# temperature.net
KiCad netlist of a schematic drawn in EAGLE
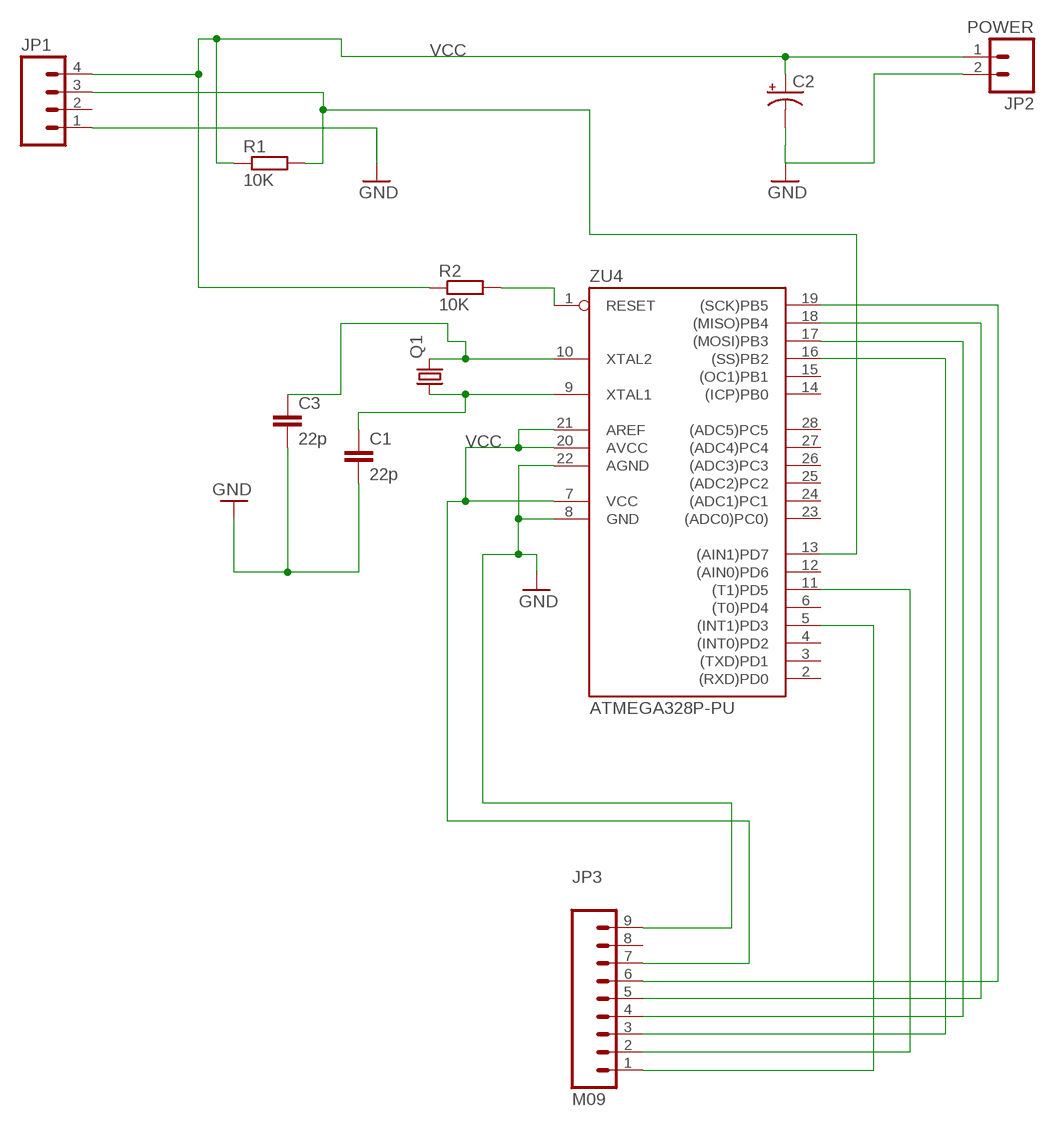
[diagram p0: schematic, sheet 1]

(export (version "E")
  (design (tool "Eeschema 10.0.6"))
  (components
    (comp (ref "C1")
      (value "22p")
      (footprint "eagle-import:C050-025X075")
      (libsource (lib "eagle-import") (part "C-EU050-025X075"))
    )
    (comp (ref "C2")
      (value "CAP_POLPTH1")
      (footprint "eagle-import:CPOL-RADIAL-100UF-25V")
      (libsource (lib "eagle-import") (part "CAP_POLPTH1"))
    )
    (comp (ref "C3")
      (value "22p")
      (footprint "eagle-import:C050-025X075")
      (libsource (lib "eagle-import") (part "C-EU050-025X075"))
    )
    (comp (ref "JP1")
      (value "M04PTH")
      (footprint "eagle-import:1X04")
      (libsource (lib "eagle-import") (part "M04PTH"))
    )
    (comp (ref "JP2")
      (value "POWER")
      (footprint "eagle-import:1X02")
      (libsource (lib "eagle-import") (part "M02PTH"))
    )
    (comp (ref "JP3")
      (value "M09")
      (footprint "eagle-import:1X09")
      (libsource (lib "eagle-import") (part "M09"))
    )
    (comp (ref "Q1")
      (value "CRYSTALHC49S")
      (footprint "eagle-import:HC49_S")
      (libsource (lib "eagle-import") (part "CRYSTALHC49S"))
    )
    (comp (ref "R1")
      (value "10K")
      (footprint "eagle-import:0207_7")
      (libsource (lib "eagle-import") (part "R-EU_0207/7"))
    )
    (comp (ref "R2")
      (value "10K")
      (footprint "eagle-import:0207_7")
      (libsource (lib "eagle-import") (part "R-EU_0207/7"))
    )
    (comp (ref "ZU4")
      (value "ATMEGA328P-PU")
      (footprint "eagle-import:DIL28-3")
      (libsource (lib "eagle-import") (part "ATMEGA328P-PU"))
    )
  )
  (nets
    (net (code "1") (name "/VCC") (class "Default")
      (node (ref "C2") (pin "1") (pinfunction "+_1") (pintype "passive"))
      (node (ref "JP1") (pin "4") (pinfunction "4_4") (pintype "passive"))
      (node (ref "JP2") (pin "1") (pinfunction "1_1") (pintype "passive"))
      (node (ref "JP3") (pin "7") (pinfunction "7_7") (pintype "passive"))
      (node (ref "R1") (pin "1") (pinfunction "1_1") (pintype "passive"))
      (node (ref "R2") (pin "1") (pinfunction "1_1") (pintype "passive"))
      (node (ref "ZU4") (pin "20") (pinfunction "AVCC_20") (pintype "power_in"))
      (node (ref "ZU4") (pin "21") (pinfunction "AREF_21") (pintype "passive"))
      (node (ref "ZU4") (pin "7") (pinfunction "VCC_7") (pintype "power_in"))
    )
    (net (code "2") (name "GND") (class "Default")
      (node (ref "C1") (pin "2") (pinfunction "2_2") (pintype "passive"))
      (node (ref "C2") (pin "2") (pinfunction "-_2") (pintype "passive"))
      (node (ref "C3") (pin "2") (pinfunction "2_2") (pintype "passive"))
      (node (ref "JP1") (pin "1") (pinfunction "1_1") (pintype "passive"))
      (node (ref "JP2") (pin "2") (pinfunction "2_2") (pintype "passive"))
      (node (ref "JP3") (pin "9") (pinfunction "9_9") (pintype "passive"))
      (node (ref "ZU4") (pin "22") (pinfunction "AGND_22") (pintype "power_in"))
      (node (ref "ZU4") (pin "8") (pinfunction "GND_8") (pintype "power_in"))
    )
    (net (code "3") (name "Net-(ZU4-(AIN1)PD7)") (class "Default")
      (node (ref "JP1") (pin "3") (pinfunction "3_3") (pintype "passive"))
      (node (ref "R1") (pin "2") (pinfunction "2_2") (pintype "passive"))
      (node (ref "ZU4") (pin "13") (pinfunction "(AIN1)PD7_13") (pintype "bidirectional"))
    )
    (net (code "4") (name "Net-(ZU4-(INT1)PD3)") (class "Default")
      (node (ref "JP3") (pin "1") (pinfunction "1_1") (pintype "passive"))
      (node (ref "ZU4") (pin "5") (pinfunction "(INT1)PD3_5") (pintype "bidirectional"))
    )
    (net (code "5") (name "Net-(ZU4-(MISO)PB4)") (class "Default")
      (node (ref "JP3") (pin "5") (pinfunction "5_5") (pintype "passive"))
      (node (ref "ZU4") (pin "18") (pinfunction "(MISO)PB4_18") (pintype "bidirectional"))
    )
    (net (code "6") (name "Net-(ZU4-(MOSI)PB3)") (class "Default")
      (node (ref "JP3") (pin "4") (pinfunction "4_4") (pintype "passive"))
      (node (ref "ZU4") (pin "17") (pinfunction "(MOSI)PB3_17") (pintype "bidirectional"))
    )
    (net (code "7") (name "Net-(ZU4-(SCK)PB5)") (class "Default")
      (node (ref "JP3") (pin "6") (pinfunction "6_6") (pintype "passive"))
      (node (ref "ZU4") (pin "19") (pinfunction "(SCK)PB5_19") (pintype "bidirectional"))
    )
    (net (code "8") (name "Net-(ZU4-(SS)PB2)") (class "Default")
      (node (ref "JP3") (pin "3") (pinfunction "3_3") (pintype "passive"))
      (node (ref "ZU4") (pin "16") (pinfunction "(SS)PB2_16") (pintype "bidirectional"))
    )
    (net (code "9") (name "Net-(ZU4-(T1)PD5)") (class "Default")
      (node (ref "JP3") (pin "2") (pinfunction "2_2") (pintype "passive"))
      (node (ref "ZU4") (pin "11") (pinfunction "(T1)PD5_11") (pintype "bidirectional"))
    )
    (net (code "10") (name "Net-(ZU4-RESET)") (class "Default")
      (node (ref "R2") (pin "2") (pinfunction "2_2") (pintype "passive"))
      (node (ref "ZU4") (pin "1") (pinfunction "RESET_1") (pintype "input"))
    )
    (net (code "11") (name "Net-(ZU4-XTAL1)") (class "Default")
      (node (ref "C1") (pin "1") (pinfunction "1_1") (pintype "passive"))
      (node (ref "Q1") (pin "1") (pinfunction "1_1") (pintype "passive"))
      (node (ref "ZU4") (pin "9") (pinfunction "XTAL1_9") (pintype "bidirectional"))
    )
    (net (code "12") (name "Net-(ZU4-XTAL2)") (class "Default")
      (node (ref "C3") (pin "1") (pinfunction "1_1") (pintype "passive"))
      (node (ref "Q1") (pin "2") (pinfunction "2_2") (pintype "passive"))
      (node (ref "ZU4") (pin "10") (pinfunction "XTAL2_10") (pintype "bidirectional"))
    )
    (net (code "13") (name "unconnected-(JP1-Pad2)") (class "Default")
      (node (ref "JP1") (pin "2") (pinfunction "2_2") (pintype "passive"))
    )
    (net (code "14") (name "unconnected-(JP3-Pad8)") (class "Default")
      (node (ref "JP3") (pin "8") (pinfunction "8_8") (pintype "passive"))
    )
    (net (code "15") (name "unconnected-(ZU4-(ADC0)PC0)-Pad23)") (class "Default")
      (node (ref "ZU4") (pin "23") (pinfunction "(ADC0)PC0)_23") (pintype "bidirectional"))
    )
    (net (code "16") (name "unconnected-(ZU4-(ADC1)PC1-Pad24)") (class "Default")
      (node (ref "ZU4") (pin "24") (pinfunction "(ADC1)PC1_24") (pintype "bidirectional"))
    )
    (net (code "17") (name "unconnected-(ZU4-(ADC2)PC2-Pad25)") (class "Default")
      (node (ref "ZU4") (pin "25") (pinfunction "(ADC2)PC2_25") (pintype "bidirectional"))
    )
    (net (code "18") (name "unconnected-(ZU4-(ADC3)PC3-Pad26)") (class "Default")
      (node (ref "ZU4") (pin "26") (pinfunction "(ADC3)PC3_26") (pintype "bidirectional"))
    )
    (net (code "19") (name "unconnected-(ZU4-(ADC4)PC4-Pad27)") (class "Default")
      (node (ref "ZU4") (pin "27") (pinfunction "(ADC4)PC4_27") (pintype "bidirectional"))
    )
    (net (code "20") (name "unconnected-(ZU4-(ADC5)PC5-Pad28)") (class "Default")
      (node (ref "ZU4") (pin "28") (pinfunction "(ADC5)PC5_28") (pintype "bidirectional"))
    )
    (net (code "21") (name "unconnected-(ZU4-(AIN0)PD6-Pad12)") (class "Default")
      (node (ref "ZU4") (pin "12") (pinfunction "(AIN0)PD6_12") (pintype "bidirectional"))
    )
    (net (code "22") (name "unconnected-(ZU4-(ICP)PB0-Pad14)") (class "Default")
      (node (ref "ZU4") (pin "14") (pinfunction "(ICP)PB0_14") (pintype "bidirectional"))
    )
    (net (code "23") (name "unconnected-(ZU4-(INT0)PD2-Pad4)") (class "Default")
      (node (ref "ZU4") (pin "4") (pinfunction "(INT0)PD2_4") (pintype "bidirectional"))
    )
    (net (code "24") (name "unconnected-(ZU4-(OC1)PB1-Pad15)") (class "Default")
      (node (ref "ZU4") (pin "15") (pinfunction "(OC1)PB1_15") (pintype "bidirectional"))
    )
    (net (code "25") (name "unconnected-(ZU4-(RXD)PD0-Pad2)") (class "Default")
      (node (ref "ZU4") (pin "2") (pinfunction "(RXD)PD0_2") (pintype "bidirectional"))
    )
    (net (code "26") (name "unconnected-(ZU4-(T0)PD4-Pad6)") (class "Default")
      (node (ref "ZU4") (pin "6") (pinfunction "(T0)PD4_6") (pintype "bidirectional"))
    )
    (net (code "27") (name "unconnected-(ZU4-(TXD)PD1-Pad3)") (class "Default")
      (node (ref "ZU4") (pin "3") (pinfunction "(TXD)PD1_3") (pintype "bidirectional"))
    )
  )
)
